# DICO_giangrandi_flipped_v100.net
KiCad netlist of a schematic drawn in EAGLE
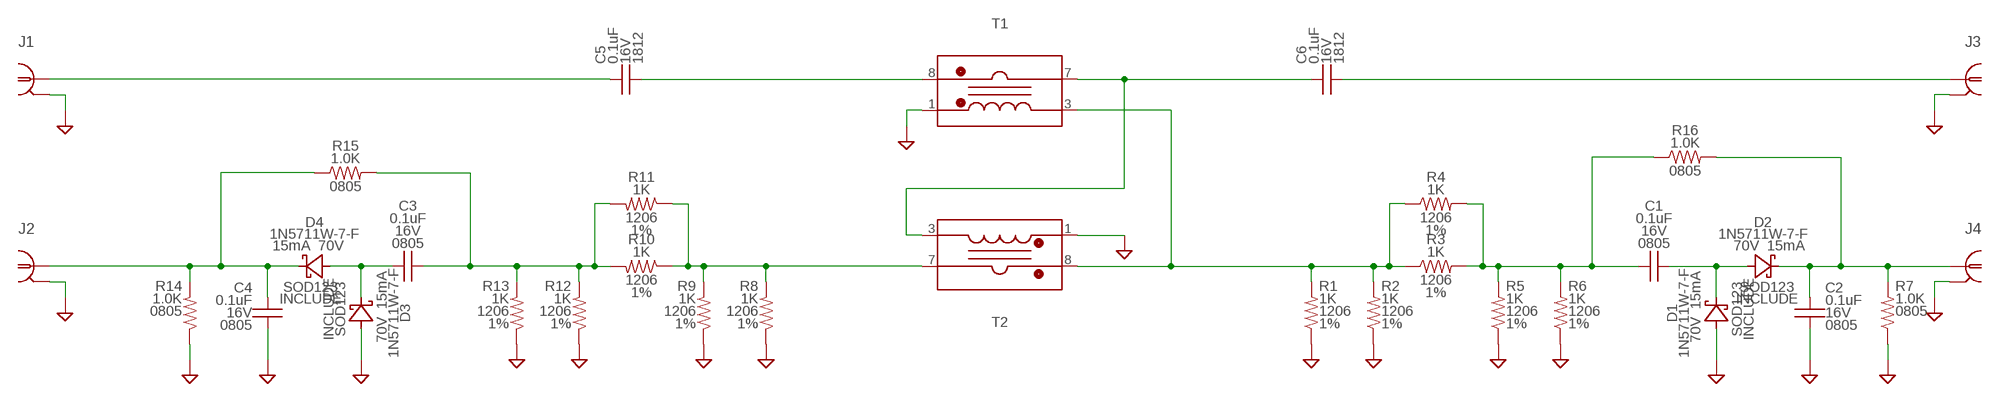
[diagram p0: schematic, sheet 1]

(export (version "E")
  (design (tool "Eeschema 10.0.6"))
  (components
    (comp (ref "C1")
      (value "0.1uF")
      (footprint "eagle-import:0805_IPC-7351B")
      (fields (field (name "PACKAGE") "0805") (field (name "VOLTAGE") "16V"))
      (libsource (lib "eagle-import") (part "C0805_IPCC-0.1U-16V-0805-X7R"))
    )
    (comp (ref "C2")
      (value "0.1uF")
      (footprint "eagle-import:0805_IPC-7351B")
      (fields (field (name "VOLTAGE") "16V"))
      (libsource (lib "eagle-import") (part "C0805_IPCC-0.1U-16V-0805-X7R"))
    )
    (comp (ref "C3")
      (value "0.1uF")
      (footprint "eagle-import:0805_IPC-7351B")
      (fields (field (name "PACKAGE") "0805") (field (name "VOLTAGE") "16V"))
      (libsource (lib "eagle-import") (part "C0805_IPCC-0.1U-16V-0805-X7R"))
    )
    (comp (ref "C4")
      (value "0.1uF")
      (footprint "eagle-import:0805_IPC-7351B")
      (fields (field (name "VOLTAGE") "16V"))
      (libsource (lib "eagle-import") (part "C0805_IPCC-0.1U-16V-0805-X7R"))
    )
    (comp (ref "C5")
      (value "0.1uF")
      (footprint "eagle-import:C1812")
      (fields (field (name "VOLTAGE") "16V"))
      (libsource (lib "eagle-import") (part "CC1812"))
    )
    (comp (ref "C6")
      (value "0.1uF")
      (footprint "eagle-import:C1812")
      (fields (field (name "VOLTAGE") "16V"))
      (libsource (lib "eagle-import") (part "CC1812"))
    )
    (comp (ref "D1")
      (value "D-SCHOTTKY1N5711W-7-FSOD123")
      (footprint "eagle-import:SOD123")
      (fields (field (name "PARTNO") "1N5711W-7-F") (field (name "VOLTAGE") "70V"))
      (libsource (lib "eagle-import") (part "D-SCHOTTKYSOD1231N5711W-7-F"))
    )
    (comp (ref "D2")
      (value "D-SCHOTTKY1N5711W-7-FSOD123")
      (footprint "eagle-import:SOD123")
      (fields (field (name "PARTNO") "1N5711W-7-F") (field (name "VOLTAGE") "70V"))
      (libsource (lib "eagle-import") (part "D-SCHOTTKYSOD1231N5711W-7-F"))
    )
    (comp (ref "D3")
      (value "D-SCHOTTKY1N5711W-7-FSOD123")
      (footprint "eagle-import:SOD123")
      (fields (field (name "PARTNO") "1N5711W-7-F") (field (name "VOLTAGE") "70V"))
      (libsource (lib "eagle-import") (part "D-SCHOTTKYSOD1231N5711W-7-F"))
    )
    (comp (ref "D4")
      (value "D-SCHOTTKY1N5711W-7-FSOD123")
      (footprint "eagle-import:SOD123")
      (fields (field (name "PARTNO") "1N5711W-7-F") (field (name "VOLTAGE") "70V"))
      (libsource (lib "eagle-import") (part "D-SCHOTTKYSOD1231N5711W-7-F"))
    )
    (comp (ref "J1")
      (value "COAXBNC_EDGE")
      (footprint "eagle-import:BNC_EDGE")
      (libsource (lib "eagle-import") (part "COAXBNC_EDGE"))
    )
    (comp (ref "J2")
      (value "COAXBNC_EDGE")
      (footprint "eagle-import:BNC_EDGE")
      (libsource (lib "eagle-import") (part "COAXBNC_EDGE"))
    )
    (comp (ref "J3")
      (value "COAXBNC_EDGE")
      (footprint "eagle-import:BNC_EDGE")
      (libsource (lib "eagle-import") (part "COAXBNC_EDGE"))
    )
    (comp (ref "J4")
      (value "COAXBNC_EDGE")
      (footprint "eagle-import:BNC_EDGE")
      (libsource (lib "eagle-import") (part "COAXBNC_EDGE"))
    )
    (comp (ref "R1")
      (value "1K")
      (footprint "eagle-import:1206_IPC-7351B")
      (fields (field (name "POWER") "0.25"))
      (libsource (lib "eagle-import") (part "R1206_IPCR-1.0K-1%-1206-0.25W"))
    )
    (comp (ref "R2")
      (value "1K")
      (footprint "eagle-import:1206_IPC-7351B")
      (fields (field (name "POWER") "0.25"))
      (libsource (lib "eagle-import") (part "R1206_IPCR-1.0K-1%-1206-0.25W"))
    )
    (comp (ref "R3")
      (value "1K")
      (footprint "eagle-import:1206_IPC-7351B")
      (fields (field (name "POWER") "0.25"))
      (libsource (lib "eagle-import") (part "R901206_IPCR-1.0K-1%-1206-0.25W"))
    )
    (comp (ref "R4")
      (value "1K")
      (footprint "eagle-import:1206_IPC-7351B")
      (fields (field (name "POWER") "0.25"))
      (libsource (lib "eagle-import") (part "R901206_IPCR-1.0K-1%-1206-0.25W"))
    )
    (comp (ref "R5")
      (value "1K")
      (footprint "eagle-import:1206_IPC-7351B")
      (fields (field (name "POWER") "0.25"))
      (libsource (lib "eagle-import") (part "R1206_IPCR-1.0K-1%-1206-0.25W"))
    )
    (comp (ref "R6")
      (value "1K")
      (footprint "eagle-import:1206_IPC-7351B")
      (fields (field (name "POWER") "0.25"))
      (libsource (lib "eagle-import") (part "R1206_IPCR-1.0K-1%-1206-0.25W"))
    )
    (comp (ref "R7")
      (value "1.0K")
      (footprint "eagle-import:0805_IPC-7351B")
      (libsource (lib "eagle-import") (part "R0805_IPCR-1.0K-0.1%-0805-0.1W"))
    )
    (comp (ref "R8")
      (value "1K")
      (footprint "eagle-import:1206_IPC-7351B")
      (fields (field (name "POWER") "0.25"))
      (libsource (lib "eagle-import") (part "R1206_IPCR-1.0K-1%-1206-0.25W"))
    )
    (comp (ref "R9")
      (value "1K")
      (footprint "eagle-import:1206_IPC-7351B")
      (fields (field (name "POWER") "0.25"))
      (libsource (lib "eagle-import") (part "R1206_IPCR-1.0K-1%-1206-0.25W"))
    )
    (comp (ref "R10")
      (value "1K")
      (footprint "eagle-import:1206_IPC-7351B")
      (fields (field (name "POWER") "0.25"))
      (libsource (lib "eagle-import") (part "R901206_IPCR-1.0K-1%-1206-0.25W"))
    )
    (comp (ref "R11")
      (value "1K")
      (footprint "eagle-import:1206_IPC-7351B")
      (fields (field (name "POWER") "0.25"))
      (libsource (lib "eagle-import") (part "R901206_IPCR-1.0K-1%-1206-0.25W"))
    )
    (comp (ref "R12")
      (value "1K")
      (footprint "eagle-import:1206_IPC-7351B")
      (fields (field (name "POWER") "0.25"))
      (libsource (lib "eagle-import") (part "R1206_IPCR-1.0K-1%-1206-0.25W"))
    )
    (comp (ref "R13")
      (value "1K")
      (footprint "eagle-import:1206_IPC-7351B")
      (fields (field (name "POWER") "0.25"))
      (libsource (lib "eagle-import") (part "R1206_IPCR-1.0K-1%-1206-0.25W"))
    )
    (comp (ref "R14")
      (value "1.0K")
      (footprint "eagle-import:0805_IPC-7351B")
      (libsource (lib "eagle-import") (part "R0805_IPCR-1.0K-0.1%-0805-0.1W"))
    )
    (comp (ref "R15")
      (value "1.0K")
      (footprint "eagle-import:0805_IPC-7351B")
      (libsource (lib "eagle-import") (part "R900805_IPCR-1.0K-0.1%-0805-0.1W"))
    )
    (comp (ref "R16")
      (value "1.0K")
      (footprint "eagle-import:0805_IPC-7351B")
      (libsource (lib "eagle-import") (part "R900805_IPCR-1.0K-0.1%-0805-0.1W"))
    )
    (comp (ref "T1")
      (value "TRAFO_CURRENTSENSEPA1005_NOCENTERPADS")
      (footprint "eagle-import:PA1005_NOCENTERPADS")
      (libsource (lib "eagle-import") (part "TRAFO_CURRENTSENSEPA1005_NOCENTERPADS"))
    )
    (comp (ref "T2")
      (value "TRAFO_CURRENTSENSEPA1005_NOCENTERPADS")
      (footprint "eagle-import:PA1005_NOCENTERPADS")
      (libsource (lib "eagle-import") (part "TRAFO_CURRENTSENSEPA1005_NOCENTERPADS"))
    )
  )
  (nets
    (net (code "1") (name "GND") (class "Default")
      (node (ref "C2") (pin "2") (pinfunction "2_2") (pintype "passive"))
      (node (ref "C4") (pin "2") (pinfunction "2_2") (pintype "passive"))
      (node (ref "D1") (pin "A") (pinfunction "A1_A") (pintype "passive"))
      (node (ref "D3") (pin "A") (pinfunction "A1_A") (pintype "passive"))
      (node (ref "J1") (pin "G1") (pinfunction "GND1_G1") (pintype "power_in"))
      (node (ref "J1") (pin "G2") (pinfunction "GND1_G2") (pintype "power_in"))
      (node (ref "J1") (pin "G3") (pinfunction "GND1_G3") (pintype "power_in"))
      (node (ref "J1") (pin "G4") (pinfunction "GND1_G4") (pintype "power_in"))
      (node (ref "J2") (pin "G1") (pinfunction "GND1_G1") (pintype "power_in"))
      (node (ref "J2") (pin "G2") (pinfunction "GND1_G2") (pintype "power_in"))
      (node (ref "J2") (pin "G3") (pinfunction "GND1_G3") (pintype "power_in"))
      (node (ref "J2") (pin "G4") (pinfunction "GND1_G4") (pintype "power_in"))
      (node (ref "J3") (pin "G1") (pinfunction "GND1_G1") (pintype "power_in"))
      (node (ref "J3") (pin "G2") (pinfunction "GND1_G2") (pintype "power_in"))
      (node (ref "J3") (pin "G3") (pinfunction "GND1_G3") (pintype "power_in"))
      (node (ref "J3") (pin "G4") (pinfunction "GND1_G4") (pintype "power_in"))
      (node (ref "J4") (pin "G1") (pinfunction "GND1_G1") (pintype "power_in"))
      (node (ref "J4") (pin "G2") (pinfunction "GND1_G2") (pintype "power_in"))
      (node (ref "J4") (pin "G3") (pinfunction "GND1_G3") (pintype "power_in"))
      (node (ref "J4") (pin "G4") (pinfunction "GND1_G4") (pintype "power_in"))
      (node (ref "R1") (pin "2") (pinfunction "2_2") (pintype "passive"))
      (node (ref "R12") (pin "2") (pinfunction "2_2") (pintype "passive"))
      (node (ref "R13") (pin "2") (pinfunction "2_2") (pintype "passive"))
      (node (ref "R14") (pin "2") (pinfunction "2_2") (pintype "passive"))
      (node (ref "R2") (pin "2") (pinfunction "2_2") (pintype "passive"))
      (node (ref "R5") (pin "2") (pinfunction "2_2") (pintype "passive"))
      (node (ref "R6") (pin "2") (pinfunction "2_2") (pintype "passive"))
      (node (ref "R7") (pin "2") (pinfunction "2_2") (pintype "passive"))
      (node (ref "R8") (pin "2") (pinfunction "2_2") (pintype "passive"))
      (node (ref "R9") (pin "2") (pinfunction "2_2") (pintype "passive"))
      (node (ref "T1") (pin "1") (pinfunction "SS_1") (pintype "passive"))
      (node (ref "T2") (pin "1") (pinfunction "SS_1") (pintype "passive"))
    )
    (net (code "2") (name "Net-(C1-Pad1)") (class "Default")
      (node (ref "C1") (pin "1") (pinfunction "1_1") (pintype "passive"))
      (node (ref "R16") (pin "1") (pinfunction "1_1") (pintype "passive"))
      (node (ref "R3") (pin "2") (pinfunction "2_2") (pintype "passive"))
      (node (ref "R4") (pin "2") (pinfunction "2_2") (pintype "passive"))
      (node (ref "R5") (pin "1") (pinfunction "1_1") (pintype "passive"))
      (node (ref "R6") (pin "1") (pinfunction "1_1") (pintype "passive"))
    )
    (net (code "3") (name "Net-(C3-Pad1)") (class "Default")
      (node (ref "C3") (pin "1") (pinfunction "1_1") (pintype "passive"))
      (node (ref "R10") (pin "2") (pinfunction "2_2") (pintype "passive"))
      (node (ref "R11") (pin "2") (pinfunction "2_2") (pintype "passive"))
      (node (ref "R12") (pin "1") (pinfunction "1_1") (pintype "passive"))
      (node (ref "R13") (pin "1") (pinfunction "1_1") (pintype "passive"))
      (node (ref "R15") (pin "2") (pinfunction "2_2") (pintype "passive"))
    )
    (net (code "4") (name "Net-(D1-C1)") (class "Default")
      (node (ref "C1") (pin "2") (pinfunction "2_2") (pintype "passive"))
      (node (ref "D1") (pin "K") (pinfunction "C1_K") (pintype "passive"))
      (node (ref "D2") (pin "A") (pinfunction "A1_A") (pintype "passive"))
    )
    (net (code "5") (name "Net-(D2-C1)") (class "Default")
      (node (ref "C2") (pin "1") (pinfunction "1_1") (pintype "passive"))
      (node (ref "D2") (pin "K") (pinfunction "C1_K") (pintype "passive"))
      (node (ref "J4") (pin "C") (pinfunction "1_C") (pintype "passive"))
      (node (ref "R16") (pin "2") (pinfunction "2_2") (pintype "passive"))
      (node (ref "R7") (pin "1") (pinfunction "1_1") (pintype "passive"))
    )
    (net (code "6") (name "Net-(D3-C1)") (class "Default")
      (node (ref "C3") (pin "2") (pinfunction "2_2") (pintype "passive"))
      (node (ref "D3") (pin "K") (pinfunction "C1_K") (pintype "passive"))
      (node (ref "D4") (pin "A") (pinfunction "A1_A") (pintype "passive"))
    )
    (net (code "7") (name "Net-(D4-C1)") (class "Default")
      (node (ref "C4") (pin "1") (pinfunction "1_1") (pintype "passive"))
      (node (ref "D4") (pin "K") (pinfunction "C1_K") (pintype "passive"))
      (node (ref "J2") (pin "C") (pinfunction "1_C") (pintype "passive"))
      (node (ref "R14") (pin "1") (pinfunction "1_1") (pintype "passive"))
      (node (ref "R15") (pin "1") (pinfunction "1_1") (pintype "passive"))
    )
    (net (code "8") (name "Net-(J1-1)") (class "Default")
      (node (ref "C5") (pin "1") (pinfunction "1_1") (pintype "passive"))
      (node (ref "J1") (pin "C") (pinfunction "1_C") (pintype "passive"))
    )
    (net (code "9") (name "Net-(J3-1)") (class "Default")
      (node (ref "C6") (pin "2") (pinfunction "2_2") (pintype "passive"))
      (node (ref "J3") (pin "C") (pinfunction "1_C") (pintype "passive"))
    )
    (net (code "10") (name "Net-(T1-PF)") (class "Default")
      (node (ref "C6") (pin "1") (pinfunction "1_1") (pintype "passive"))
      (node (ref "T1") (pin "7") (pinfunction "PF_7") (pintype "passive"))
      (node (ref "T2") (pin "3") (pinfunction "SF_3") (pintype "passive"))
    )
    (net (code "11") (name "Net-(T1-PS)") (class "Default")
      (node (ref "C5") (pin "2") (pinfunction "2_2") (pintype "passive"))
      (node (ref "T1") (pin "8") (pinfunction "PS_8") (pintype "passive"))
    )
    (net (code "12") (name "Net-(T1-SF)") (class "Default")
      (node (ref "R1") (pin "1") (pinfunction "1_1") (pintype "passive"))
      (node (ref "R2") (pin "1") (pinfunction "1_1") (pintype "passive"))
      (node (ref "R3") (pin "1") (pinfunction "1_1") (pintype "passive"))
      (node (ref "R4") (pin "1") (pinfunction "1_1") (pintype "passive"))
      (node (ref "T1") (pin "3") (pinfunction "SF_3") (pintype "passive"))
      (node (ref "T2") (pin "8") (pinfunction "PS_8") (pintype "passive"))
    )
    (net (code "13") (name "Net-(T2-PF)") (class "Default")
      (node (ref "R10") (pin "1") (pinfunction "1_1") (pintype "passive"))
      (node (ref "R11") (pin "1") (pinfunction "1_1") (pintype "passive"))
      (node (ref "R8") (pin "1") (pinfunction "1_1") (pintype "passive"))
      (node (ref "R9") (pin "1") (pinfunction "1_1") (pintype "passive"))
      (node (ref "T2") (pin "7") (pinfunction "PF_7") (pintype "passive"))
    )
  )
)
